# Temperature_Sensors.net
KiCad netlist of a schematic drawn in Altium Designer
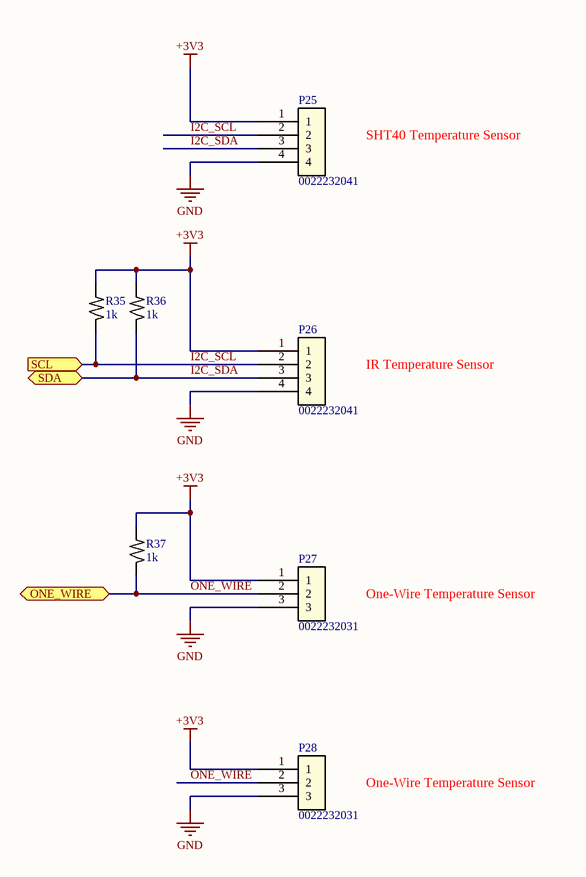
[diagram p0: Temperature Sensors.SchDoc]

(export (version "E")
  (design (tool "Eeschema 10.0.6"))
  (components
    (comp (ref "P25")
      (value "0022232041")
      (footprint "Signal4")
      (description "SignalConnector, 4 leads")
      (fields (field (name "MF") "Molex"))
      (libsource (lib "Connectors") (part "Signal4"))
    )
    (comp (ref "P26")
      (value "0022232041")
      (footprint "Signal4")
      (description "SignalConnector, 4 leads")
      (fields (field (name "MF") "Molex"))
      (libsource (lib "Connectors") (part "Signal4"))
    )
    (comp (ref "P27")
      (value "0022232031")
      (footprint "Signal3")
      (description "SignalConnector, 3 leads")
      (fields (field (name "MF") "Molex"))
      (libsource (lib "Connectors") (part "Signal3"))
    )
    (comp (ref "P28")
      (value "0022232031")
      (footprint "Signal3")
      (description "SignalConnector, 3 leads")
      (fields (field (name "MF") "Molex"))
      (libsource (lib "Connectors") (part "Signal3"))
    )
    (comp (ref "R35")
      (value "1k")
      (footprint "R0603")
      (description "RES 1kΩ ±5% 100mW 0603")
      (fields (field (name "MF") "VO") (field (name "MP") "SCR0603J1K"))
      (libsource (lib "Components") (part "Res"))
    )
    (comp (ref "R36")
      (value "1k")
      (footprint "R0603")
      (description "RES 1kΩ ±5% 100mW 0603")
      (fields (field (name "MF") "VO") (field (name "MP") "SCR0603J1K"))
      (libsource (lib "Components") (part "Res"))
    )
    (comp (ref "R37")
      (value "1k")
      (footprint "R0603")
      (description "RES 1kΩ ±5% 100mW 0603")
      (fields (field (name "MF") "VO") (field (name "MP") "SCR0603J1K"))
      (libsource (lib "Components") (part "Res"))
    )
  )
  (nets
    (net (code "1") (name "+3V3") (class "Default")
      (node (ref "P25") (pin "1") (pinfunction "1_1") (pintype "passive"))
      (node (ref "P26") (pin "1") (pinfunction "1_1") (pintype "passive"))
      (node (ref "P27") (pin "1") (pinfunction "1_1") (pintype "passive"))
      (node (ref "P28") (pin "1") (pinfunction "1_1") (pintype "passive"))
      (node (ref "R35") (pin "1") (pinfunction "1_1") (pintype "passive"))
      (node (ref "R36") (pin "1") (pinfunction "1_1") (pintype "passive"))
      (node (ref "R37") (pin "1") (pinfunction "1_1") (pintype "passive"))
    )
    (net (code "2") (name "/I2C_SCL") (class "Default")
      (node (ref "P25") (pin "2") (pinfunction "2_2") (pintype "passive"))
      (node (ref "P26") (pin "2") (pinfunction "2_2") (pintype "passive"))
      (node (ref "R35") (pin "2") (pinfunction "2_2") (pintype "passive"))
    )
    (net (code "3") (name "/I2C_SDA") (class "Default")
      (node (ref "P25") (pin "3") (pinfunction "3_3") (pintype "passive"))
      (node (ref "P26") (pin "3") (pinfunction "3_3") (pintype "passive"))
      (node (ref "R36") (pin "2") (pinfunction "2_2") (pintype "passive"))
    )
    (net (code "4") (name "/ONE_WIRE") (class "Default")
      (node (ref "P27") (pin "2") (pinfunction "2_2") (pintype "passive"))
      (node (ref "P28") (pin "2") (pinfunction "2_2") (pintype "passive"))
      (node (ref "R37") (pin "2") (pinfunction "2_2") (pintype "passive"))
    )
    (net (code "5") (name "GND") (class "Default")
      (node (ref "P25") (pin "4") (pinfunction "4_4") (pintype "passive"))
      (node (ref "P26") (pin "4") (pinfunction "4_4") (pintype "passive"))
      (node (ref "P27") (pin "3") (pinfunction "3_3") (pintype "passive"))
      (node (ref "P28") (pin "3") (pinfunction "3_3") (pintype "passive"))
    )
  )
)
